# SC10033E1_2.net
KiCad netlist of a schematic drawn in Altium Designer
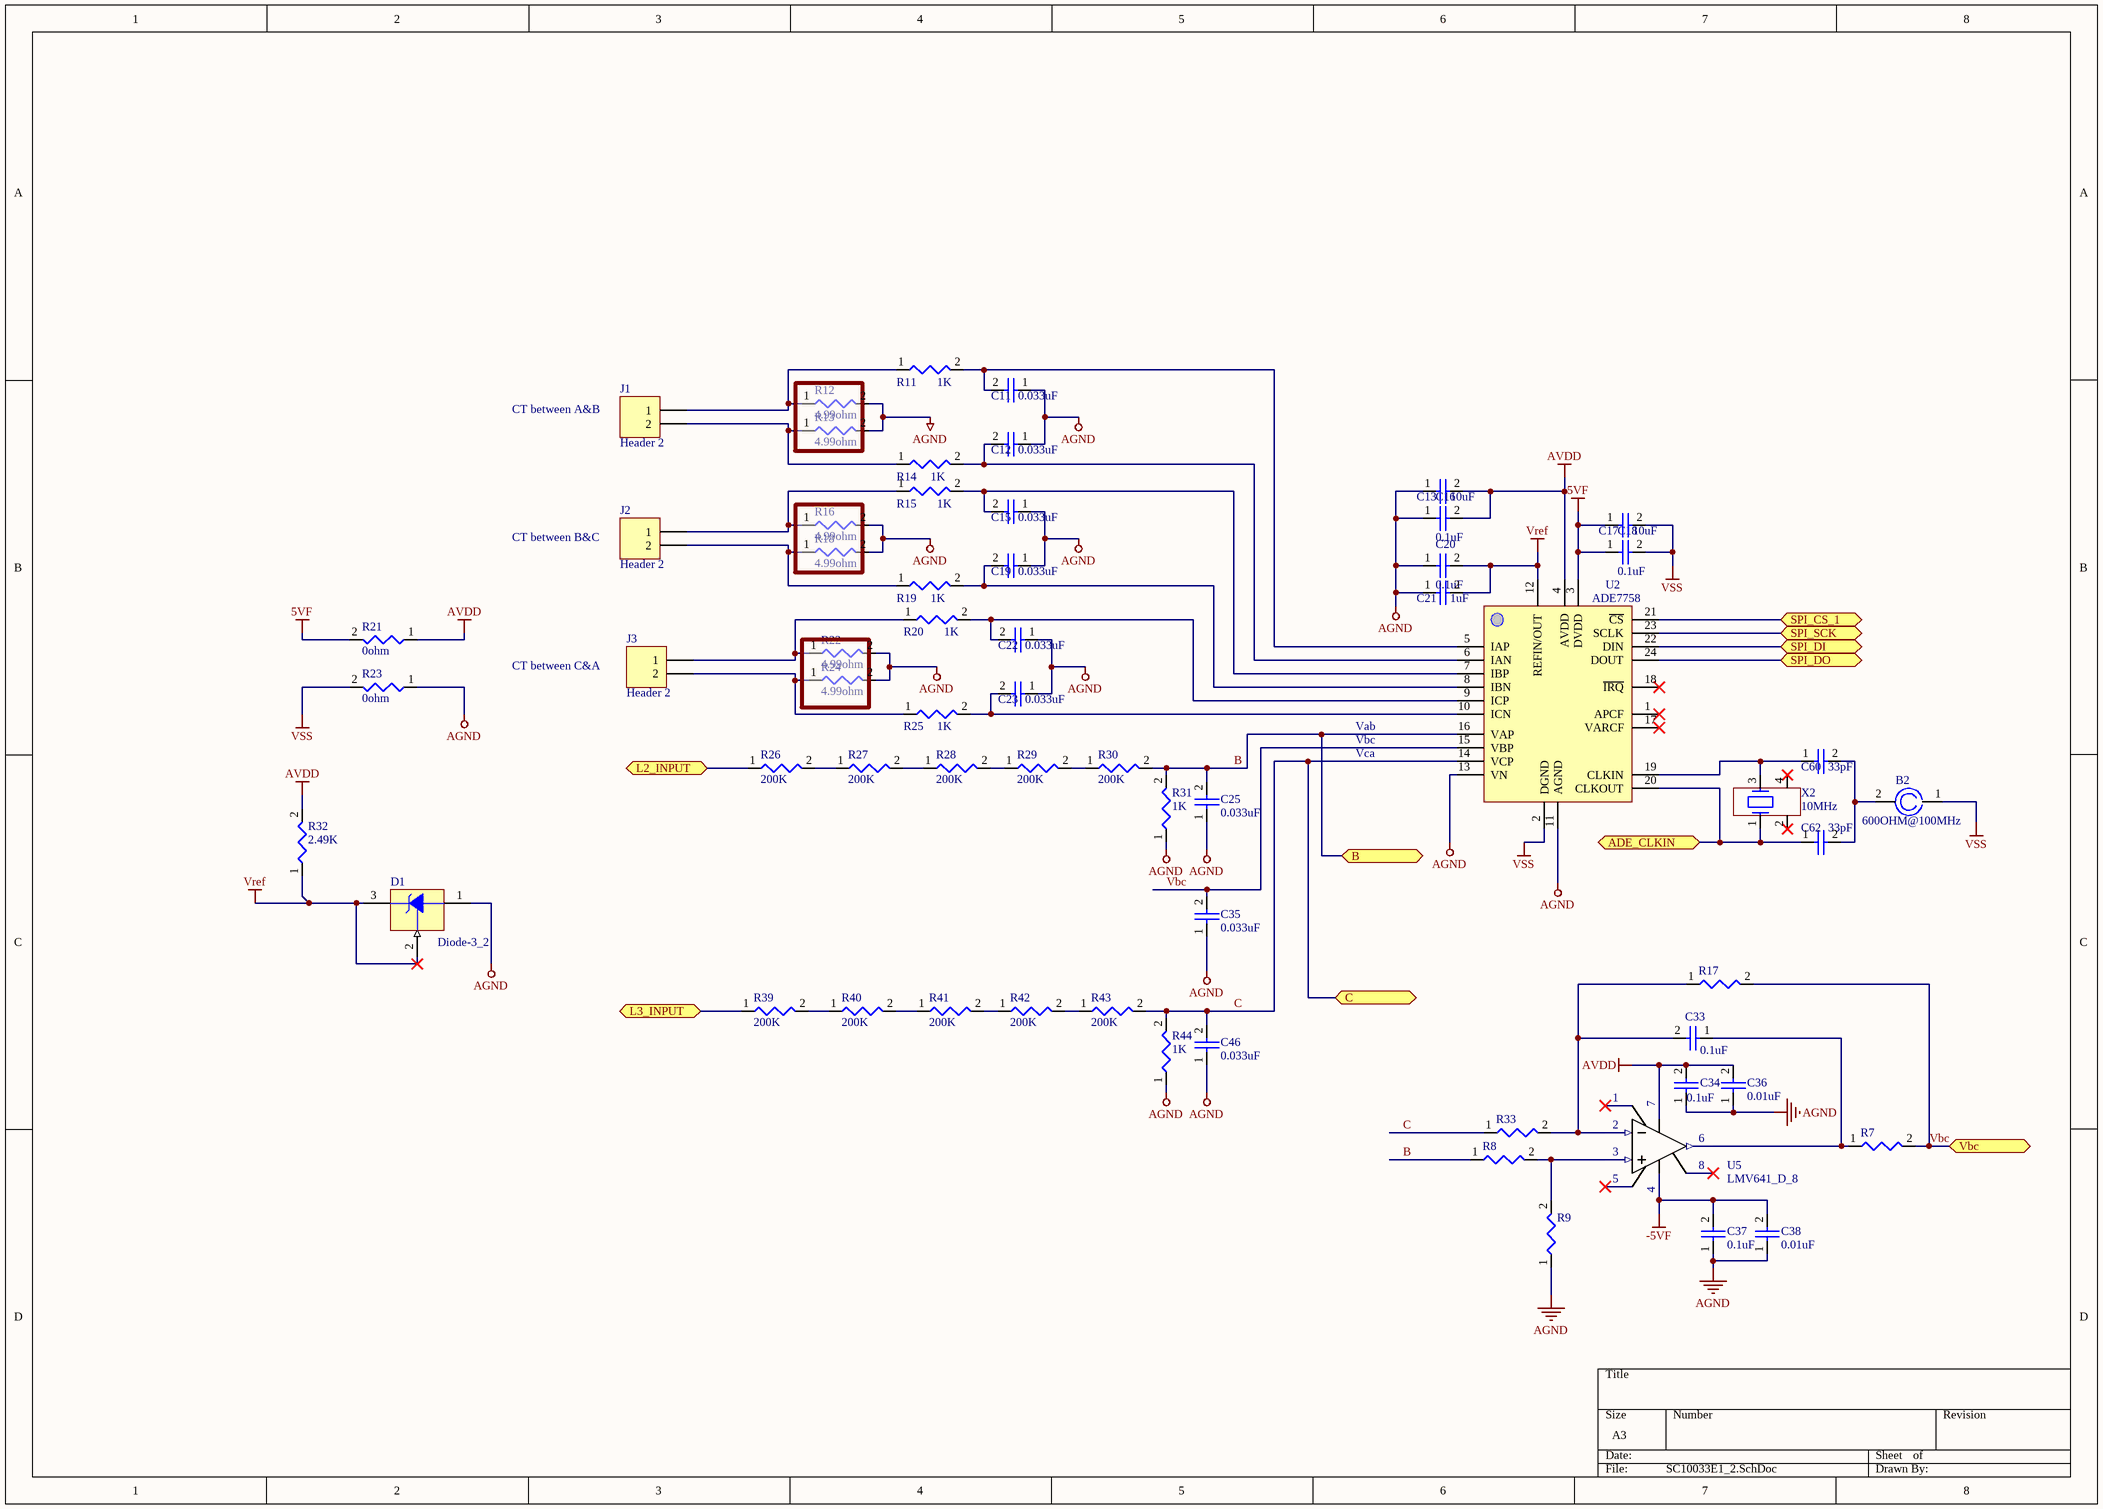
[diagram p0: SC10033E1_2.SchDoc]

(export (version "E")
  (design (tool "Eeschema 10.0.6"))
  (components
    (comp (ref "B2")
      (value "600OHM@100MHz")
      (footprint "L0805")
      (description "Ferrite Bead 600OHM@100MHz 200mA SMD 0805 ROHS")
      (fields (field (name "MANUFACTURER") "Wuerth Electronic") (field (name "Comment") "FERRITE"))
      (libsource (lib "enlogic") (part "FERRITE"))
    )
    (comp (ref "C11")
      (value "0.033uF")
      (footprint "C0805")
      (description "CAP SMD X7R 50V 10% 0.033uF 0805 ROHS")
      (fields (field (name "MANUFACTURER") "Murata") (field (name "Comment") "CAP"))
      (libsource (lib "enlogic") (part "CAP"))
    )
    (comp (ref "C12")
      (value "0.033uF")
      (footprint "C0805")
      (description "CAP SMD X7R 50V 10% 0.033uF 0805 ROHS")
      (fields (field (name "MANUFACTURER") "Murata") (field (name "Comment") "CAP"))
      (libsource (lib "enlogic") (part "CAP"))
    )
    (comp (ref "C13")
      (value "10uF")
      (footprint "C0805")
      (description "CAP SMD CR X5R 16V 10% 10uF 0805 ROHS")
      (fields (field (name "MANUFACTURER") "Murata"))
      (libsource (lib "enlogic") (part "CAP"))
    )
    (comp (ref "C15")
      (value "0.033uF")
      (footprint "C0805")
      (description "CAP SMD X7R 50V 10% 0.033uF 0805 ROHS")
      (fields (field (name "MANUFACTURER") "Murata") (field (name "Comment") "CAP"))
      (libsource (lib "enlogic") (part "CAP"))
    )
    (comp (ref "C16")
      (value "0.1uF")
      (footprint "C0805")
      (description "CAP SMD CR X7R 50V 10% 0.1uF 0805 ROHS")
      (fields (field (name "MANUFACTURER") "YAGEO") (field (name "Comment") "CAP"))
      (libsource (lib "enlogic") (part "CAP"))
    )
    (comp (ref "C17")
      (value "10uF")
      (footprint "C0805")
      (description "CAP SMD CR X5R 16V 10% 10uF 0805 ROHS")
      (fields (field (name "MANUFACTURER") "Murata"))
      (libsource (lib "enlogic") (part "CAP"))
    )
    (comp (ref "C18")
      (value "0.1uF")
      (footprint "C0805")
      (description "CAP SMD CR X7R 50V 10% 0.1uF 0805 ROHS")
      (fields (field (name "MANUFACTURER") "YAGEO") (field (name "Comment") "CAP"))
      (libsource (lib "enlogic") (part "CAP"))
    )
    (comp (ref "C19")
      (value "0.033uF")
      (footprint "C0805")
      (description "CAP SMD X7R 50V 10% 0.033uF 0805 ROHS")
      (fields (field (name "MANUFACTURER") "Murata") (field (name "Comment") "CAP"))
      (libsource (lib "enlogic") (part "CAP"))
    )
    (comp (ref "C20")
      (value "0.1uF")
      (footprint "C0805")
      (description "CAP SMD CR X7R 50V 10% 0.1uF 0805 ROHS")
      (fields (field (name "MANUFACTURER") "YAGEO") (field (name "Comment") "CAP"))
      (libsource (lib "enlogic") (part "CAP"))
    )
    (comp (ref "C21")
      (value "1uF")
      (footprint "C0805")
      (description "CAP SMD CR X7R 50V 10% 1uF 0805 ROHS")
      (fields (field (name "MANUFACTURER") "YAGEO") (field (name "Comment") "CAP"))
      (libsource (lib "enlogic") (part "CAP"))
    )
    (comp (ref "C22")
      (value "0.033uF")
      (footprint "C0805")
      (description "CAP SMD X7R 50V 10% 0.033uF 0805 ROHS")
      (fields (field (name "MANUFACTURER") "Murata") (field (name "Comment") "CAP"))
      (libsource (lib "enlogic") (part "CAP"))
    )
    (comp (ref "C23")
      (value "0.033uF")
      (footprint "C0805")
      (description "CAP SMD X7R 50V 10% 0.033uF 0805 ROHS")
      (fields (field (name "MANUFACTURER") "Murata") (field (name "Comment") "CAP"))
      (libsource (lib "enlogic") (part "CAP"))
    )
    (comp (ref "C25")
      (value "0.033uF")
      (footprint "C0805")
      (description "CAP SMD X7R 50V 10% 0.033uF 0805 ROHS")
      (fields (field (name "MANUFACTURER") "Murata") (field (name "Comment") "CAP"))
      (libsource (lib "enlogic") (part "CAP"))
    )
    (comp (ref "C33")
      (value "0.1uF")
      (footprint "C0805")
      (description "CAP SMD CR X7R 50V 10% 0.1uF 0805 ROHS")
      (fields (field (name "MANUFACTURER") "Murata") (field (name "Comment") "CAP"))
      (libsource (lib "enlogic") (part "CAP"))
    )
    (comp (ref "C34")
      (value "0.1uF")
      (footprint "C0805")
      (description "CAP SMD CR X7R 50V 10% 0.1uF 0805 ROHS")
      (fields (field (name "MANUFACTURER") "Murata") (field (name "Comment") "CAP"))
      (libsource (lib "enlogic") (part "CAP"))
    )
    (comp (ref "C35")
      (value "0.033uF")
      (footprint "C0805")
      (description "CAP SMD X7R 50V 10% 0.033uF 0805 ROHS")
      (fields (field (name "MANUFACTURER") "Murata") (field (name "Comment") "CAP"))
      (libsource (lib "enlogic") (part "CAP"))
    )
    (comp (ref "C36")
      (value "0.01uF")
      (footprint "C0805")
      (description "CAP SMD CR X7R 50V 10% 10nF 0805 ROHS")
      (fields (field (name "MANUFACTURER") "Murata") (field (name "Comment") "CAP"))
      (libsource (lib "enlogic") (part "CAP"))
    )
    (comp (ref "C37")
      (value "0.1uF")
      (footprint "C0805")
      (description "CAP SMD CR X7R 50V 10% 0.1uF 0805 ROHS")
      (fields (field (name "MANUFACTURER") "Murata") (field (name "Comment") "CAP"))
      (libsource (lib "enlogic") (part "CAP"))
    )
    (comp (ref "C38")
      (value "0.01uF")
      (footprint "C0805")
      (description "CAP SMD CR X7R 50V 10% 10nF 0805 ROHS")
      (fields (field (name "MANUFACTURER") "Murata") (field (name "Comment") "CAP"))
      (libsource (lib "enlogic") (part "CAP"))
    )
    (comp (ref "C46")
      (value "0.033uF")
      (footprint "C0805")
      (description "CAP SMD X7R 50V 10% 0.033uF 0805 ROHS")
      (fields (field (name "MANUFACTURER") "Murata") (field (name "Comment") "CAP"))
      (libsource (lib "enlogic") (part "CAP"))
    )
    (comp (ref "C60")
      (value "33pF")
      (footprint "C0805")
      (description "CAP SMD C0G 50V 5% 33pF 0805 ROHS")
      (fields (field (name "MANUFACTURER") "YAGEO") (field (name "Comment") "CAP"))
      (libsource (lib "enlogic") (part "CAP"))
    )
    (comp (ref "C62")
      (value "33pF")
      (footprint "C0805")
      (description "CAP SMD C0G 50V 5% 33pF 0805 ROHS")
      (fields (field (name "MANUFACTURER") "YAGEO") (field (name "Comment") "CAP"))
      (libsource (lib "enlogic") (part "CAP"))
    )
    (comp (ref "D1")
      (value "Diode-3_2")
      (footprint "SOT23-321")
      (description "IC PROGRAMMABLE PRECISION REFERENCES,2.5-20V,0.5%,SMD,ROHS")
      (fields (field (name "MANUFACTURER") "DIODES"))
      (libsource (lib "enlogic") (part "ZTL43X"))
    )
    (comp (ref "J1")
      (value "Header 2")
      (footprint "533980271_sd")
      (description "CONNECTOR 1.25mm Pitch Header, Surface Mount, Vertical, Lead-Free, 2 Circuits")
      (fields (field (name "MANUFACTURER") "MOLEX"))
      (libsource (lib "enlogic") (part "Header 2"))
    )
    (comp (ref "J2")
      (value "Header 2")
      (footprint "533980271_sd")
      (description "CONNECTOR 1.25mm Pitch Header, Surface Mount, Vertical, Lead-Free, 2 Circuits")
      (fields (field (name "MANUFACTURER") "MOLEX"))
      (libsource (lib "enlogic") (part "Header 2"))
    )
    (comp (ref "J3")
      (value "Header 2")
      (footprint "533980271_sd")
      (description "CONNECTOR 1.25mm Pitch Header, Surface Mount, Vertical, Lead-Free, 2 Circuits")
      (fields (field (name "MANUFACTURER") "MOLEX"))
      (libsource (lib "enlogic") (part "Header 2"))
    )
    (comp (ref "R7")
      (value "RES")
      (footprint "R0805")
      (description "RES THICK_FILM SMD 0 OHM 5% 1/8W ROHS 0805")
      (fields (field (name "MANUFACTURER") "YAGEO"))
      (libsource (lib "enlogic") (part "RES"))
    )
    (comp (ref "R8")
      (value "RES")
      (footprint "R0603")
      (description "RES THIN_FILM SMD 10K 0.1% 1/10W ±25ppm/℃ ROHS 0603")
      (fields (field (name "MANUFACTURER") "YAGEO"))
      (libsource (lib "enlogic") (part "RES"))
    )
    (comp (ref "R9")
      (value "RES")
      (footprint "R0603")
      (description "RES THIN_FILM SMD 10K 0.1% 1/10W ±25ppm/℃ ROHS 0603")
      (fields (field (name "MANUFACTURER") "YAGEO"))
      (libsource (lib "enlogic") (part "RES"))
    )
    (comp (ref "R11")
      (value "1K")
      (footprint "R0805")
      (description "RES THICK_FILM SMD 1K 1% 1/8W ROHS 0805")
      (fields (field (name "MANUFACTURER") "YAGEO") (field (name "Comment") "RES"))
      (libsource (lib "enlogic") (part "RES"))
    )
    (comp (ref "R12")
      (value "4.99ohm")
      (footprint "R0805")
      (description "RES THIN_FILM SMD 4.99 ohm 0.1% 1/8W ±25ppm/℃ ROHS 0805")
      (fields (field (name "MANUFACTURER") "YAGEO") (field (name "Comment") "RES"))
      (libsource (lib "enlogic") (part "RES"))
    )
    (comp (ref "R13")
      (value "4.99ohm")
      (footprint "R0805")
      (description "RES THIN_FILM SMD 4.99 ohm 0.1% 1/8W ±25ppm/℃ ROHS 0805")
      (fields (field (name "MANUFACTURER") "YAGEO") (field (name "Comment") "RES"))
      (libsource (lib "enlogic") (part "RES"))
    )
    (comp (ref "R14")
      (value "1K")
      (footprint "R0805")
      (description "RES THICK_FILM SMD 1K 1% 1/8W ROHS 0805")
      (fields (field (name "MANUFACTURER") "YAGEO") (field (name "Comment") "RES"))
      (libsource (lib "enlogic") (part "RES"))
    )
    (comp (ref "R15")
      (value "1K")
      (footprint "R0805")
      (description "RES THICK_FILM SMD 1K 1% 1/8W ROHS 0805")
      (fields (field (name "MANUFACTURER") "YAGEO") (field (name "Comment") "RES"))
      (libsource (lib "enlogic") (part "RES"))
    )
    (comp (ref "R16")
      (value "4.99ohm")
      (footprint "R0805")
      (description "RES THIN_FILM SMD 4.99 ohm 0.1% 1/8W ±25ppm/℃ ROHS 0805")
      (fields (field (name "MANUFACTURER") "YAGEO") (field (name "Comment") "RES"))
      (libsource (lib "enlogic") (part "RES"))
    )
    (comp (ref "R17")
      (value "RES")
      (footprint "R0603")
      (description "RES THIN_FILM SMD 10K 0.1% 1/10W ±25ppm/℃ ROHS 0603")
      (fields (field (name "MANUFACTURER") "YAGEO"))
      (libsource (lib "enlogic") (part "RES"))
    )
    (comp (ref "R18")
      (value "4.99ohm")
      (footprint "R0805")
      (description "RES THIN_FILM SMD 4.99 ohm 0.1% 1/8W ±25ppm/℃ ROHS 0805")
      (fields (field (name "MANUFACTURER") "YAGEO") (field (name "Comment") "RES"))
      (libsource (lib "enlogic") (part "RES"))
    )
    (comp (ref "R19")
      (value "1K")
      (footprint "R0805")
      (description "RES THICK_FILM SMD 1K 1% 1/8W ROHS 0805")
      (fields (field (name "MANUFACTURER") "YAGEO") (field (name "Comment") "RES"))
      (libsource (lib "enlogic") (part "RES"))
    )
    (comp (ref "R20")
      (value "1K")
      (footprint "R0805")
      (description "RES THICK_FILM SMD 1K 1% 1/8W ROHS 0805")
      (fields (field (name "MANUFACTURER") "YAGEO") (field (name "Comment") "RES"))
      (libsource (lib "enlogic") (part "RES"))
    )
    (comp (ref "R21")
      (value "0ohm")
      (footprint "R0805")
      (description "RES THICK_FILM SMD 0 OHM 5% 1/8W ROHS 0805")
      (fields (field (name "MANUFACTURER") "YAGEO") (field (name "Comment") "RES"))
      (libsource (lib "enlogic") (part "RES"))
    )
    (comp (ref "R22")
      (value "4.99ohm")
      (footprint "R0805")
      (description "RES THIN_FILM SMD 4.99 ohm 0.1% 1/8W ±25ppm/℃ ROHS 0805")
      (fields (field (name "MANUFACTURER") "YAGEO") (field (name "Comment") "RES"))
      (libsource (lib "enlogic") (part "RES"))
    )
    (comp (ref "R23")
      (value "0ohm")
      (footprint "R0805")
      (description "RES THICK_FILM SMD 0 OHM 5% 1/8W ROHS 0805")
      (fields (field (name "MANUFACTURER") "YAGEO") (field (name "Comment") "RES"))
      (libsource (lib "enlogic") (part "RES"))
    )
    (comp (ref "R24")
      (value "4.99ohm")
      (footprint "R0805")
      (description "RES THIN_FILM SMD 4.99 ohm 0.1% 1/8W ±25ppm/℃ ROHS 0805")
      (fields (field (name "MANUFACTURER") "YAGEO") (field (name "Comment") "RES"))
      (libsource (lib "enlogic") (part "RES"))
    )
    (comp (ref "R25")
      (value "1K")
      (footprint "R0805")
      (description "RES THICK_FILM SMD 1K 1% 1/8W ROHS 0805")
      (fields (field (name "MANUFACTURER") "YAGEO") (field (name "Comment") "RES"))
      (libsource (lib "enlogic") (part "RES"))
    )
    (comp (ref "R26")
      (value "200K")
      (footprint "R0805")
      (description "RES THIN_FILM SMD 200K 0.1% 1/8W 25PPM ROHS 0805")
      (fields (field (name "MANUFACTURER") "YAGEO") (field (name "Comment") "RES"))
      (libsource (lib "enlogic") (part "RES"))
    )
    (comp (ref "R27")
      (value "200K")
      (footprint "R0805")
      (description "RES THIN_FILM SMD 200K 0.1% 1/8W 25PPM ROHS 0805")
      (fields (field (name "MANUFACTURER") "YAGEO") (field (name "Comment") "RES"))
      (libsource (lib "enlogic") (part "RES"))
    )
    (comp (ref "R28")
      (value "200K")
      (footprint "R0805")
      (description "RES THIN_FILM SMD 200K 0.1% 1/8W 25PPM ROHS 0805")
      (fields (field (name "MANUFACTURER") "YAGEO") (field (name "Comment") "RES"))
      (libsource (lib "enlogic") (part "RES"))
    )
    (comp (ref "R29")
      (value "200K")
      (footprint "R0805")
      (description "RES THIN_FILM SMD 200K 0.1% 1/8W 25PPM ROHS 0805")
      (fields (field (name "MANUFACTURER") "YAGEO") (field (name "Comment") "RES"))
      (libsource (lib "enlogic") (part "RES"))
    )
    (comp (ref "R30")
      (value "200K")
      (footprint "R0805")
      (description "RES THIN_FILM SMD 200K 0.1% 1/8W 25PPM ROHS 0805")
      (fields (field (name "MANUFACTURER") "YAGEO") (field (name "Comment") "RES"))
      (libsource (lib "enlogic") (part "RES"))
    )
    (comp (ref "R31")
      (value "1K")
      (footprint "R0805")
      (description "RES THIN_FILM 1K 0.1% 1/8W ±25ppm/℃ ROHS SMD 0805")
      (fields (field (name "MANUFACTURER") "YAGEO") (field (name "Comment") "RES"))
      (libsource (lib "enlogic") (part "RES"))
    )
    (comp (ref "R32")
      (value "2.49K")
      (footprint "R0805")
      (description "RES THICK_FILM 2.49K 1% 1/8W ROHS SMD 0805")
      (fields (field (name "MANUFACTURER") "YAGEO") (field (name "Comment") "RES"))
      (libsource (lib "enlogic") (part "RES"))
    )
    (comp (ref "R33")
      (value "RES")
      (footprint "R0603")
      (description "RES THIN_FILM SMD 10K 0.1% 1/10W ±25ppm/℃ ROHS 0603")
      (fields (field (name "MANUFACTURER") "YAGEO"))
      (libsource (lib "enlogic") (part "RES"))
    )
    (comp (ref "R39")
      (value "200K")
      (footprint "R0805")
      (description "RES THIN_FILM SMD 200K 0.1% 1/8W 25PPM ROHS 0805")
      (fields (field (name "MANUFACTURER") "YAGEO") (field (name "Comment") "RES"))
      (libsource (lib "enlogic") (part "RES"))
    )
    (comp (ref "R40")
      (value "200K")
      (footprint "R0805")
      (description "RES THIN_FILM SMD 200K 0.1% 1/8W 25PPM ROHS 0805")
      (fields (field (name "MANUFACTURER") "YAGEO") (field (name "Comment") "RES"))
      (libsource (lib "enlogic") (part "RES"))
    )
    (comp (ref "R41")
      (value "200K")
      (footprint "R0805")
      (description "RES THIN_FILM SMD 200K 0.1% 1/8W 25PPM ROHS 0805")
      (fields (field (name "MANUFACTURER") "YAGEO") (field (name "Comment") "RES"))
      (libsource (lib "enlogic") (part "RES"))
    )
    (comp (ref "R42")
      (value "200K")
      (footprint "R0805")
      (description "RES THIN_FILM SMD 200K 0.1% 1/8W 25PPM ROHS 0805")
      (fields (field (name "MANUFACTURER") "YAGEO") (field (name "Comment") "RES"))
      (libsource (lib "enlogic") (part "RES"))
    )
    (comp (ref "R43")
      (value "200K")
      (footprint "R0805")
      (description "RES THIN_FILM SMD 200K 0.1% 1/8W 25PPM ROHS 0805")
      (fields (field (name "MANUFACTURER") "YAGEO") (field (name "Comment") "RES"))
      (libsource (lib "enlogic") (part "RES"))
    )
    (comp (ref "R44")
      (value "1K")
      (footprint "R0805")
      (description "RES THIN_FILM 1K 0.1% 1/8W ±25ppm/℃ ROHS SMD 0805")
      (fields (field (name "MANUFACTURER") "YAGEO") (field (name "Comment") "RES"))
      (libsource (lib "enlogic") (part "RES"))
    )
    (comp (ref "U2")
      (value "ADE7758")
      (footprint "SOIC24-W")
      (description "IC Energy Measurement,Irms,VA,VAR,Vrms,Watt,Output:Pulsed&SPI,SOIC_W-24,ROHS")
      (fields (field (name "MANUFACTURER") "ANALOG DEVICES"))
      (libsource (lib "enlogic") (part "ADE7758"))
    )
    (comp (ref "U5")
      (value "LMV641_D_8")
      (footprint "M08A")
      (description "Op Amp,10MHz,12V,Low Power,SOIC-8,RoHS")
      (fields (field (name "MANUFACTURER") "TI"))
      (libsource (lib "enlogic") (part "LMV641_D_8"))
    )
    (comp (ref "X2")
      (value "10MHz")
      (footprint "XTAL_5X3_2")
      (description "XTAL 10MHz 18PF +/-30PPM,3.2mmWx5mmLx1.3mmH,-40~85,RoHS,SMD")
      (fields (field (name "MANUFACTURER") "ABRACON") (field (name "Comment") "ABM3C"))
      (libsource (lib "enlogic") (part "ABM3C"))
    )
  )
  (nets
    (net (code "1") (name "-5VF") (class "Default")
      (node (ref "C37") (pin "2") (pinfunction "2_2") (pintype "passive"))
      (node (ref "C38") (pin "2") (pinfunction "2_2") (pintype "passive"))
      (node (ref "U5") (pin "4") (pinfunction "V-_4") (pintype "power_in"))
    )
    (net (code "2") (name "/ADE_CLKIN") (class "Default")
      (node (ref "C62") (pin "1") (pinfunction "1_1") (pintype "passive"))
      (node (ref "U2") (pin "20") (pinfunction "CLKOUT_20") (pintype "passive"))
      (node (ref "X2") (pin "1") (pinfunction "1_1") (pintype "passive"))
    )
    (net (code "3") (name "/B") (class "Default")
      (node (ref "C25") (pin "2") (pinfunction "2_2") (pintype "passive"))
      (node (ref "R30") (pin "2") (pinfunction "2_2") (pintype "passive"))
      (node (ref "R31") (pin "2") (pinfunction "2_2") (pintype "passive"))
      (node (ref "R8") (pin "1") (pinfunction "1_1") (pintype "passive"))
      (node (ref "U2") (pin "16") (pinfunction "VAP_16") (pintype "passive"))
    )
    (net (code "4") (name "/C") (class "Default")
      (node (ref "C46") (pin "2") (pinfunction "2_2") (pintype "passive"))
      (node (ref "R33") (pin "1") (pinfunction "1_1") (pintype "passive"))
      (node (ref "R43") (pin "2") (pinfunction "2_2") (pintype "passive"))
      (node (ref "R44") (pin "2") (pinfunction "2_2") (pintype "passive"))
      (node (ref "U2") (pin "14") (pinfunction "VCP_14") (pintype "passive"))
    )
    (net (code "5") (name "/L2_INPUT") (class "Default")
      (node (ref "R26") (pin "1") (pinfunction "1_1") (pintype "passive"))
    )
    (net (code "6") (name "/L3_INPUT") (class "Default")
      (node (ref "R39") (pin "1") (pinfunction "1_1") (pintype "passive"))
    )
    (net (code "7") (name "/SPI_CS_1") (class "Default")
      (node (ref "U2") (pin "21") (pinfunction "~{CS}_21") (pintype "passive"))
    )
    (net (code "8") (name "/SPI_DI") (class "Default")
      (node (ref "U2") (pin "22") (pinfunction "DIN_22") (pintype "passive"))
    )
    (net (code "9") (name "/SPI_DO") (class "Default")
      (node (ref "U2") (pin "24") (pinfunction "DOUT_24") (pintype "passive"))
    )
    (net (code "10") (name "/SPI_SCK") (class "Default")
      (node (ref "U2") (pin "23") (pinfunction "SCLK_23") (pintype "passive"))
    )
    (net (code "11") (name "/Vbc") (class "Default")
      (node (ref "C35") (pin "2") (pinfunction "2_2") (pintype "passive"))
      (node (ref "R17") (pin "2") (pinfunction "2_2") (pintype "passive"))
      (node (ref "R7") (pin "2") (pinfunction "2_2") (pintype "passive"))
      (node (ref "U2") (pin "15") (pinfunction "VBP_15") (pintype "passive"))
    )
    (net (code "12") (name "5VF") (class "Default")
      (node (ref "C17") (pin "1") (pinfunction "1_1") (pintype "passive"))
      (node (ref "C18") (pin "1") (pinfunction "1_1") (pintype "passive"))
      (node (ref "R21") (pin "2") (pinfunction "2_2") (pintype "passive"))
      (node (ref "U2") (pin "3") (pinfunction "DVDD_3") (pintype "passive"))
    )
    (net (code "13") (name "AGND") (class "Default")
      (node (ref "C11") (pin "1") (pinfunction "1_1") (pintype "passive"))
      (node (ref "C12") (pin "1") (pinfunction "1_1") (pintype "passive"))
      (node (ref "C13") (pin "1") (pinfunction "1_1") (pintype "passive"))
      (node (ref "C15") (pin "1") (pinfunction "1_1") (pintype "passive"))
      (node (ref "C16") (pin "1") (pinfunction "1_1") (pintype "passive"))
      (node (ref "C19") (pin "1") (pinfunction "1_1") (pintype "passive"))
      (node (ref "C20") (pin "1") (pinfunction "1_1") (pintype "passive"))
      (node (ref "C21") (pin "1") (pinfunction "1_1") (pintype "passive"))
      (node (ref "C22") (pin "1") (pinfunction "1_1") (pintype "passive"))
      (node (ref "C23") (pin "1") (pinfunction "1_1") (pintype "passive"))
      (node (ref "C25") (pin "1") (pinfunction "1_1") (pintype "passive"))
      (node (ref "C34") (pin "1") (pinfunction "1_1") (pintype "passive"))
      (node (ref "C35") (pin "1") (pinfunction "1_1") (pintype "passive"))
      (node (ref "C36") (pin "1") (pinfunction "1_1") (pintype "passive"))
      (node (ref "C37") (pin "1") (pinfunction "1_1") (pintype "passive"))
      (node (ref "C38") (pin "1") (pinfunction "1_1") (pintype "passive"))
      (node (ref "C46") (pin "1") (pinfunction "1_1") (pintype "passive"))
      (node (ref "D1") (pin "1") (pinfunction "A_1") (pintype "passive"))
      (node (ref "R12") (pin "2") (pinfunction "2_2") (pintype "passive"))
      (node (ref "R13") (pin "2") (pinfunction "2_2") (pintype "passive"))
      (node (ref "R16") (pin "2") (pinfunction "2_2") (pintype "passive"))
      (node (ref "R18") (pin "2") (pinfunction "2_2") (pintype "passive"))
      (node (ref "R22") (pin "2") (pinfunction "2_2") (pintype "passive"))
      (node (ref "R23") (pin "1") (pinfunction "1_1") (pintype "passive"))
      (node (ref "R24") (pin "2") (pinfunction "2_2") (pintype "passive"))
      (node (ref "R31") (pin "1") (pinfunction "1_1") (pintype "passive"))
      (node (ref "R44") (pin "1") (pinfunction "1_1") (pintype "passive"))
      (node (ref "R9") (pin "1") (pinfunction "1_1") (pintype "passive"))
      (node (ref "U2") (pin "11") (pinfunction "AGND_11") (pintype "passive"))
      (node (ref "U2") (pin "13") (pinfunction "VN_13") (pintype "passive"))
    )
    (net (code "14") (name "AVDD") (class "Default")
      (node (ref "C13") (pin "2") (pinfunction "2_2") (pintype "passive"))
      (node (ref "C16") (pin "2") (pinfunction "2_2") (pintype "passive"))
      (node (ref "C34") (pin "2") (pinfunction "2_2") (pintype "passive"))
      (node (ref "C36") (pin "2") (pinfunction "2_2") (pintype "passive"))
      (node (ref "R21") (pin "1") (pinfunction "1_1") (pintype "passive"))
      (node (ref "R32") (pin "2") (pinfunction "2_2") (pintype "passive"))
      (node (ref "U2") (pin "4") (pinfunction "AVDD_4") (pintype "passive"))
      (node (ref "U5") (pin "7") (pinfunction "V+_7") (pintype "power_in"))
    )
    (net (code "15") (name "Net-(B2-Pad2)") (class "Default")
      (node (ref "B2") (pin "2") (pinfunction "2_2") (pintype "passive"))
      (node (ref "C60") (pin "2") (pinfunction "2_2") (pintype "passive"))
      (node (ref "C62") (pin "2") (pinfunction "2_2") (pintype "passive"))
    )
    (net (code "16") (name "Net-(J1-Pad1)") (class "Default")
      (node (ref "J1") (pin "1") (pinfunction "1_1") (pintype "passive"))
      (node (ref "R11") (pin "1") (pinfunction "1_1") (pintype "passive"))
      (node (ref "R12") (pin "1") (pinfunction "1_1") (pintype "passive"))
    )
    (net (code "17") (name "Net-(J1-Pad2)") (class "Default")
      (node (ref "J1") (pin "2") (pinfunction "2_2") (pintype "passive"))
      (node (ref "R13") (pin "1") (pinfunction "1_1") (pintype "passive"))
      (node (ref "R14") (pin "1") (pinfunction "1_1") (pintype "passive"))
    )
    (net (code "18") (name "Net-(J2-Pad1)") (class "Default")
      (node (ref "J2") (pin "1") (pinfunction "1_1") (pintype "passive"))
      (node (ref "R15") (pin "1") (pinfunction "1_1") (pintype "passive"))
      (node (ref "R16") (pin "1") (pinfunction "1_1") (pintype "passive"))
    )
    (net (code "19") (name "Net-(J2-Pad2)") (class "Default")
      (node (ref "J2") (pin "2") (pinfunction "2_2") (pintype "passive"))
      (node (ref "R18") (pin "1") (pinfunction "1_1") (pintype "passive"))
      (node (ref "R19") (pin "1") (pinfunction "1_1") (pintype "passive"))
    )
    (net (code "20") (name "Net-(J3-Pad1)") (class "Default")
      (node (ref "J3") (pin "1") (pinfunction "1_1") (pintype "passive"))
      (node (ref "R20") (pin "1") (pinfunction "1_1") (pintype "passive"))
      (node (ref "R22") (pin "1") (pinfunction "1_1") (pintype "passive"))
    )
    (net (code "21") (name "Net-(J3-Pad2)") (class "Default")
      (node (ref "J3") (pin "2") (pinfunction "2_2") (pintype "passive"))
      (node (ref "R24") (pin "1") (pinfunction "1_1") (pintype "passive"))
      (node (ref "R25") (pin "1") (pinfunction "1_1") (pintype "passive"))
    )
    (net (code "22") (name "Net-(R26-Pad2)") (class "Default")
      (node (ref "R26") (pin "2") (pinfunction "2_2") (pintype "passive"))
      (node (ref "R27") (pin "1") (pinfunction "1_1") (pintype "passive"))
    )
    (net (code "23") (name "Net-(R27-Pad2)") (class "Default")
      (node (ref "R27") (pin "2") (pinfunction "2_2") (pintype "passive"))
      (node (ref "R28") (pin "1") (pinfunction "1_1") (pintype "passive"))
    )
    (net (code "24") (name "Net-(R28-Pad2)") (class "Default")
      (node (ref "R28") (pin "2") (pinfunction "2_2") (pintype "passive"))
      (node (ref "R29") (pin "1") (pinfunction "1_1") (pintype "passive"))
    )
    (net (code "25") (name "Net-(R29-Pad2)") (class "Default")
      (node (ref "R29") (pin "2") (pinfunction "2_2") (pintype "passive"))
      (node (ref "R30") (pin "1") (pinfunction "1_1") (pintype "passive"))
    )
    (net (code "26") (name "Net-(R39-Pad2)") (class "Default")
      (node (ref "R39") (pin "2") (pinfunction "2_2") (pintype "passive"))
      (node (ref "R40") (pin "1") (pinfunction "1_1") (pintype "passive"))
    )
    (net (code "27") (name "Net-(R40-Pad2)") (class "Default")
      (node (ref "R40") (pin "2") (pinfunction "2_2") (pintype "passive"))
      (node (ref "R41") (pin "1") (pinfunction "1_1") (pintype "passive"))
    )
    (net (code "28") (name "Net-(R41-Pad2)") (class "Default")
      (node (ref "R41") (pin "2") (pinfunction "2_2") (pintype "passive"))
      (node (ref "R42") (pin "1") (pinfunction "1_1") (pintype "passive"))
    )
    (net (code "29") (name "Net-(R42-Pad2)") (class "Default")
      (node (ref "R42") (pin "2") (pinfunction "2_2") (pintype "passive"))
      (node (ref "R43") (pin "1") (pinfunction "1_1") (pintype "passive"))
    )
    (net (code "30") (name "Net-(U2-CLKIN)") (class "Default")
      (node (ref "C60") (pin "1") (pinfunction "1_1") (pintype "passive"))
      (node (ref "U2") (pin "19") (pinfunction "CLKIN_19") (pintype "passive"))
      (node (ref "X2") (pin "3") (pinfunction "3_3") (pintype "passive"))
    )
    (net (code "31") (name "Net-(U2-IAN)") (class "Default")
      (node (ref "C12") (pin "2") (pinfunction "2_2") (pintype "passive"))
      (node (ref "R14") (pin "2") (pinfunction "2_2") (pintype "passive"))
      (node (ref "U2") (pin "6") (pinfunction "IAN_6") (pintype "passive"))
    )
    (net (code "32") (name "Net-(U2-IAP)") (class "Default")
      (node (ref "C11") (pin "2") (pinfunction "2_2") (pintype "passive"))
      (node (ref "R11") (pin "2") (pinfunction "2_2") (pintype "passive"))
      (node (ref "U2") (pin "5") (pinfunction "IAP_5") (pintype "passive"))
    )
    (net (code "33") (name "Net-(U2-IBN)") (class "Default")
      (node (ref "C19") (pin "2") (pinfunction "2_2") (pintype "passive"))
      (node (ref "R19") (pin "2") (pinfunction "2_2") (pintype "passive"))
      (node (ref "U2") (pin "8") (pinfunction "IBN_8") (pintype "passive"))
    )
    (net (code "34") (name "Net-(U2-IBP)") (class "Default")
      (node (ref "C15") (pin "2") (pinfunction "2_2") (pintype "passive"))
      (node (ref "R15") (pin "2") (pinfunction "2_2") (pintype "passive"))
      (node (ref "U2") (pin "7") (pinfunction "IBP_7") (pintype "passive"))
    )
    (net (code "35") (name "Net-(U2-ICN)") (class "Default")
      (node (ref "C23") (pin "2") (pinfunction "2_2") (pintype "passive"))
      (node (ref "R25") (pin "2") (pinfunction "2_2") (pintype "passive"))
      (node (ref "U2") (pin "10") (pinfunction "ICN_10") (pintype "passive"))
    )
    (net (code "36") (name "Net-(U2-ICP)") (class "Default")
      (node (ref "C22") (pin "2") (pinfunction "2_2") (pintype "passive"))
      (node (ref "R20") (pin "2") (pinfunction "2_2") (pintype "passive"))
      (node (ref "U2") (pin "9") (pinfunction "ICP_9") (pintype "passive"))
    )
    (net (code "37") (name "Net-(U5-IN+)") (class "Default")
      (node (ref "R8") (pin "2") (pinfunction "2_2") (pintype "passive"))
      (node (ref "R9") (pin "2") (pinfunction "2_2") (pintype "passive"))
      (node (ref "U5") (pin "3") (pinfunction "IN+_3") (pintype "input"))
    )
    (net (code "38") (name "Net-(U5-IN-)") (class "Default")
      (node (ref "C33") (pin "2") (pinfunction "2_2") (pintype "passive"))
      (node (ref "R17") (pin "1") (pinfunction "1_1") (pintype "passive"))
      (node (ref "R33") (pin "2") (pinfunction "2_2") (pintype "passive"))
      (node (ref "U5") (pin "2") (pinfunction "IN-_2") (pintype "input"))
    )
    (net (code "39") (name "Net-(U5-OUT)") (class "Default")
      (node (ref "C33") (pin "1") (pinfunction "1_1") (pintype "passive"))
      (node (ref "R7") (pin "1") (pinfunction "1_1") (pintype "passive"))
      (node (ref "U5") (pin "6") (pinfunction "OUT_6") (pintype "output"))
    )
    (net (code "40") (name "VSS") (class "Default")
      (node (ref "B2") (pin "1") (pinfunction "1_1") (pintype "passive"))
      (node (ref "C17") (pin "2") (pinfunction "2_2") (pintype "passive"))
      (node (ref "C18") (pin "2") (pinfunction "2_2") (pintype "passive"))
      (node (ref "R23") (pin "2") (pinfunction "2_2") (pintype "passive"))
      (node (ref "U2") (pin "2") (pinfunction "DGND_2") (pintype "passive"))
    )
    (net (code "41") (name "Vref") (class "Default")
      (node (ref "C20") (pin "2") (pinfunction "2_2") (pintype "passive"))
      (node (ref "C21") (pin "2") (pinfunction "2_2") (pintype "passive"))
      (node (ref "D1") (pin "2") (pinfunction "R_2") (pintype "input"))
      (node (ref "D1") (pin "3") (pinfunction "C_3") (pintype "passive"))
      (node (ref "R32") (pin "1") (pinfunction "1_1") (pintype "passive"))
      (node (ref "U2") (pin "12") (pinfunction "REFIN/OUT_12") (pintype "passive"))
    )
    (net (code "42") (name "unconnected-(U2-APCF-Pad1)") (class "Default")
      (node (ref "U2") (pin "1") (pinfunction "APCF_1") (pintype "passive+no_connect"))
    )
    (net (code "43") (name "unconnected-(U2-VARCF-Pad17)") (class "Default")
      (node (ref "U2") (pin "17") (pinfunction "VARCF_17") (pintype "passive+no_connect"))
    )
    (net (code "44") (name "unconnected-(U2-~{IRQ}-Pad18)") (class "Default")
      (node (ref "U2") (pin "18") (pinfunction "~{IRQ}_18") (pintype "passive+no_connect"))
    )
    (net (code "45") (name "unconnected-(U5-NC-Pad1)") (class "Default")
      (node (ref "U5") (pin "1") (pinfunction "NC_1") (pintype "passive+no_connect"))
    )
    (net (code "46") (name "unconnected-(U5-NC_2-Pad8)") (class "Default")
      (node (ref "U5") (pin "8") (pinfunction "NC_2_8") (pintype "passive+no_connect"))
    )
    (net (code "47") (name "unconnected-(U5-NC_3-Pad5)") (class "Default")
      (node (ref "U5") (pin "5") (pinfunction "NC_3_5") (pintype "passive+no_connect"))
    )
    (net (code "48") (name "unconnected-(X2-Pad2)") (class "Default")
      (node (ref "X2") (pin "2") (pinfunction "2_2") (pintype "passive+no_connect"))
    )
    (net (code "49") (name "unconnected-(X2-Pad4)") (class "Default")
      (node (ref "X2") (pin "4") (pinfunction "4_4") (pintype "passive+no_connect"))
    )
  )
)
